# monitor-one-io-card-v0_0_4.net
KiCad netlist of a schematic drawn in EAGLE
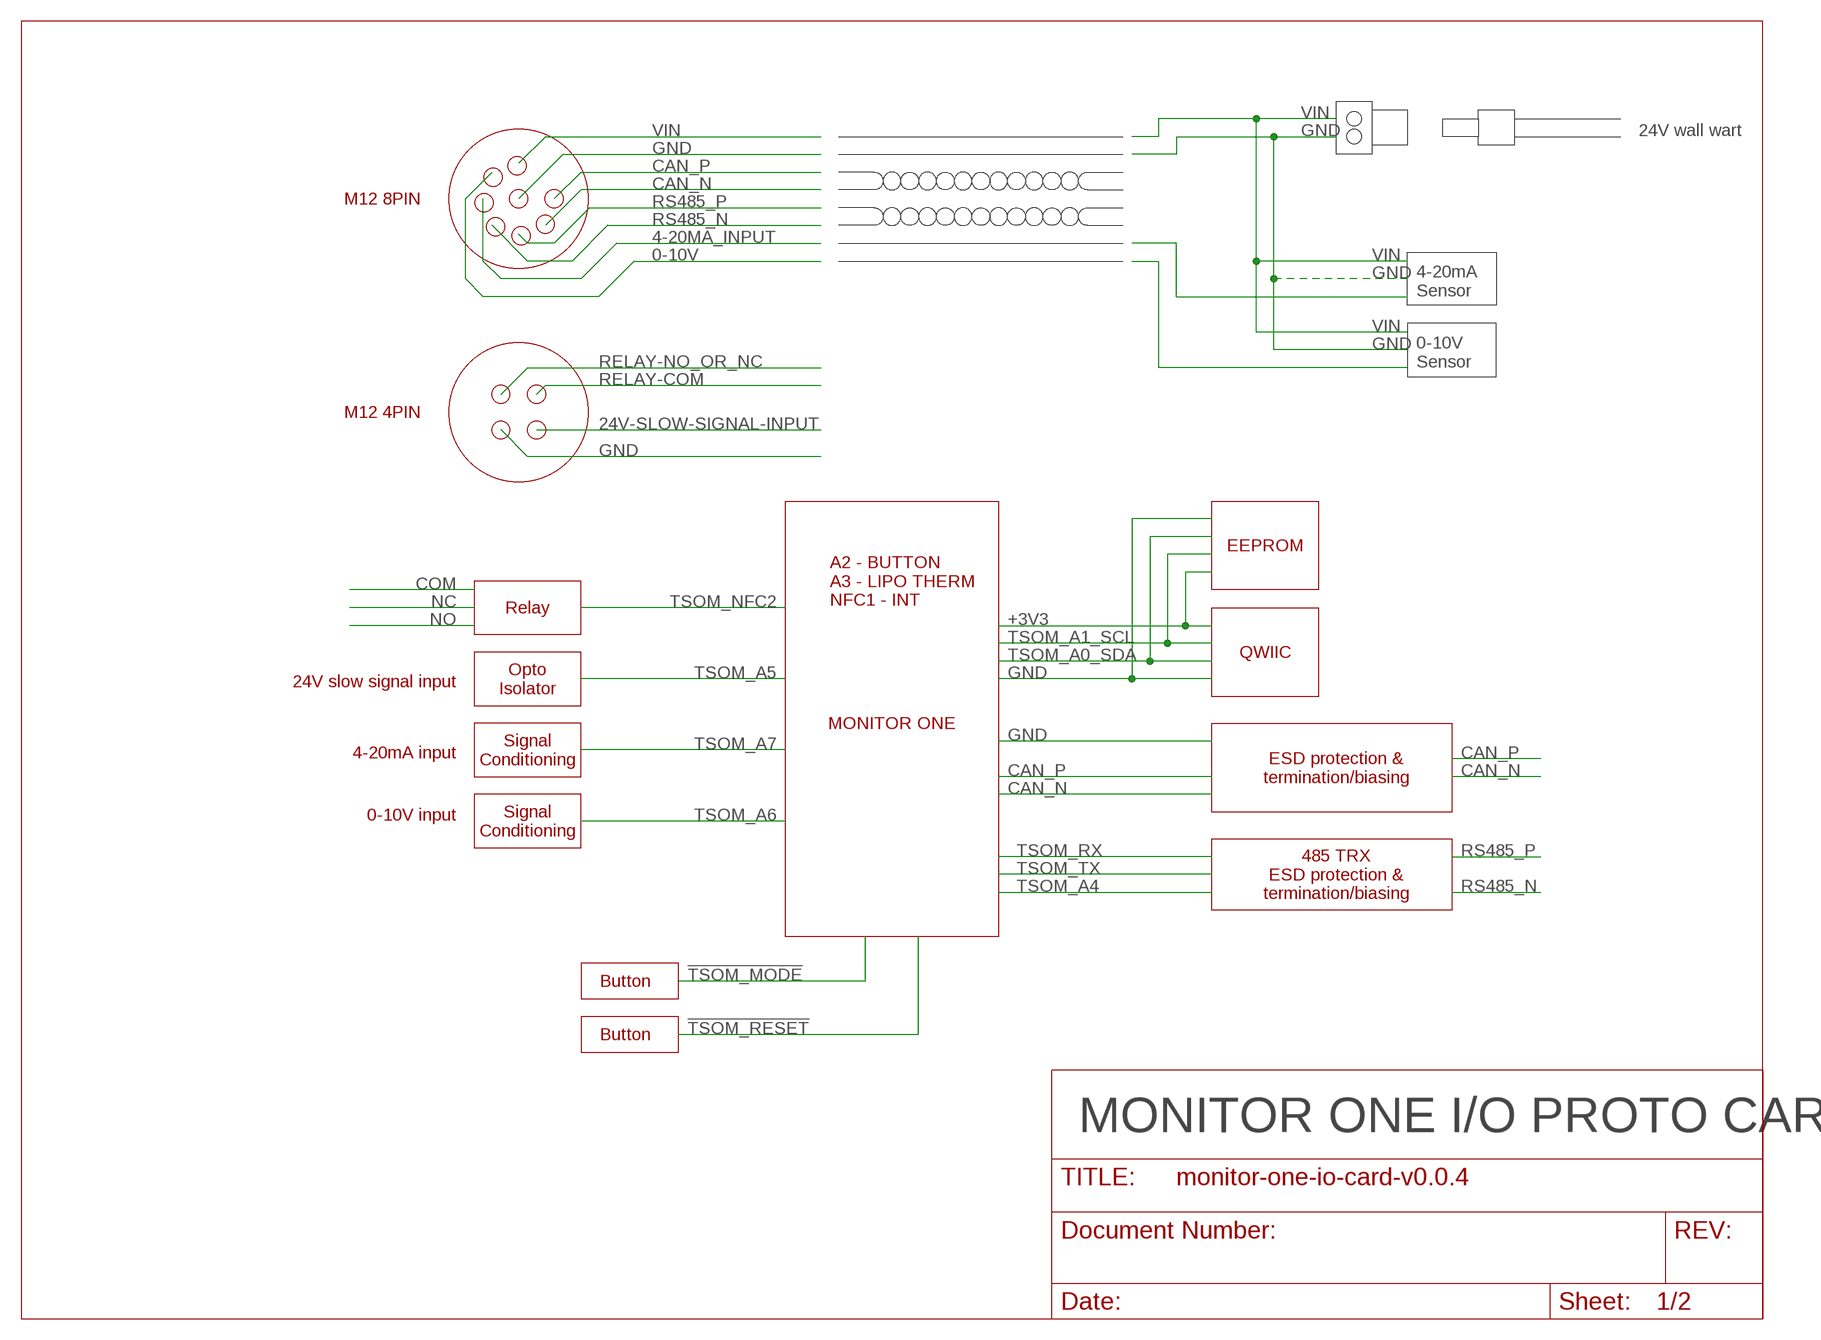
[diagram p0: schematic, sheet 1]
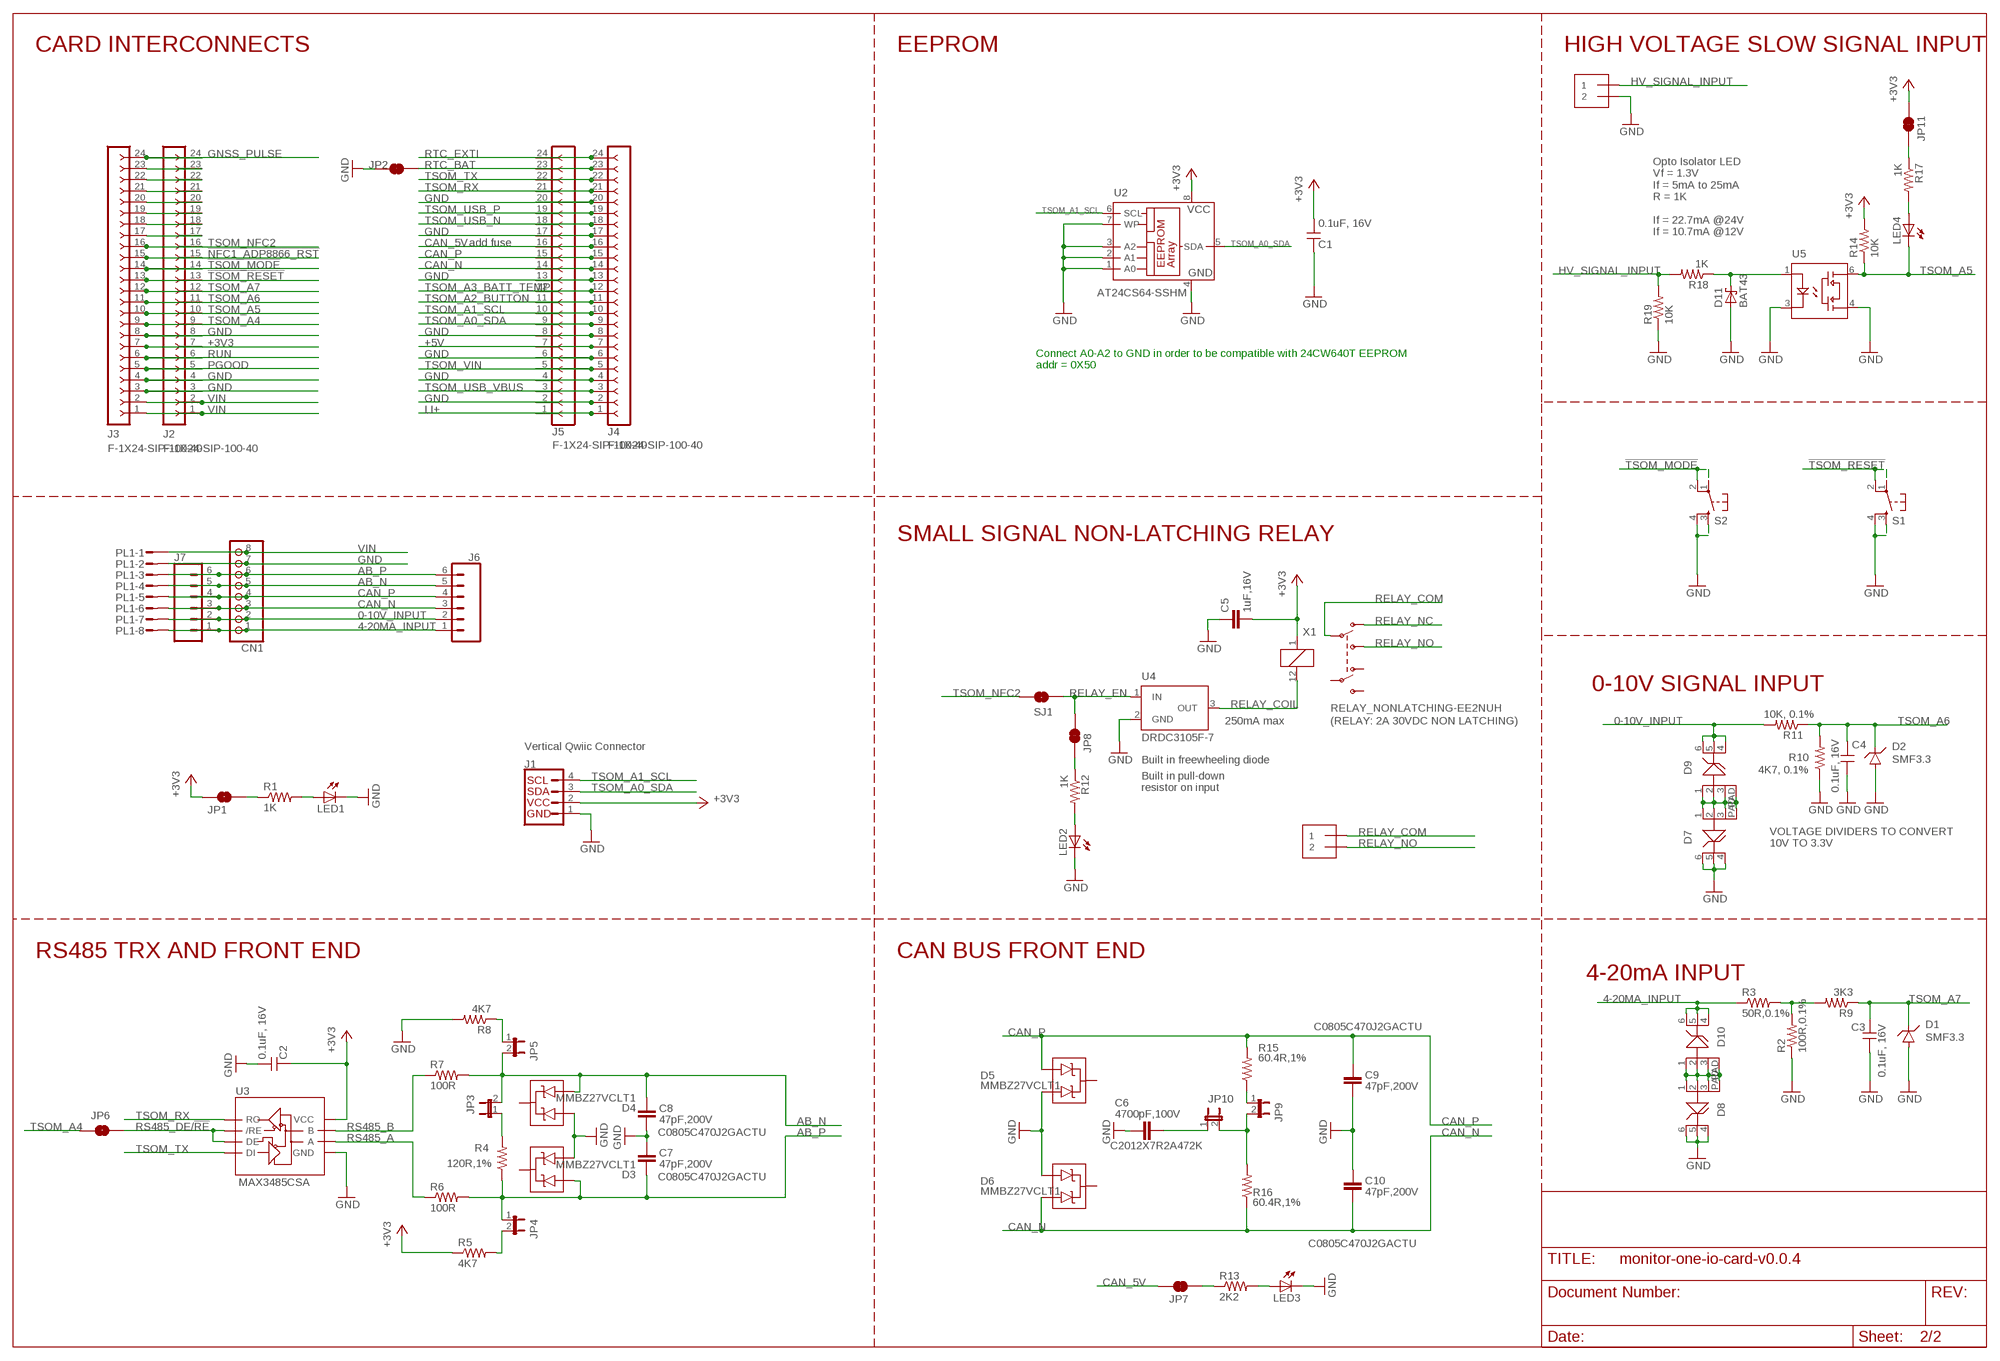
[diagram p1: schematic, sheet 2]

(export (version "E")
  (design (tool "Eeschema 10.0.6"))
  (components
    (comp (ref "C1")
      (value "0.1uF, 16V")
      (footprint "eagle-import:C0603_P")
      (fields (field (name "MFG") "FENGHUA") (field (name "MPN") "0603B104K160NT"))
      (libsource (lib "eagle-import") (part "CAP_06030.1UF_16V_"))
    )
    (comp (ref "C2")
      (value "0.1uF, 16V")
      (footprint "eagle-import:C0603_P")
      (fields (field (name "MFG") "FENGHUA") (field (name "MPN") "0603B104K160NT"))
      (libsource (lib "eagle-import") (part "CAP_06030.1UF_16V_"))
    )
    (comp (ref "C3")
      (value "0.1uF, 16V")
      (footprint "eagle-import:C0603_P")
      (fields (field (name "MFG") "FENGHUA") (field (name "MPN") "0603B104K160NT"))
      (libsource (lib "eagle-import") (part "CAP_06030.1UF_16V_"))
    )
    (comp (ref "C4")
      (value "0.1uF, 16V")
      (footprint "eagle-import:C0603_P")
      (fields (field (name "MFG") "FENGHUA") (field (name "MPN") "0603B104K160NT"))
      (libsource (lib "eagle-import") (part "CAP_06030.1UF_16V_"))
    )
    (comp (ref "C5")
      (value "1uF,16V")
      (footprint "eagle-import:C0805")
      (libsource (lib "eagle-import") (part "C-EUC0805"))
    )
    (comp (ref "C6")
      (value "4700pF,100V")
      (footprint "eagle-import:C0805")
      (fields (field (name "PART_NUMBER") "C2012X7R2A472K"))
      (libsource (lib "eagle-import") (part "C-EUC0805"))
    )
    (comp (ref "C7")
      (value "47pF,200V")
      (footprint "eagle-import:C0805")
      (fields (field (name "PART_NUMBER") "C0805C470J2GACTU"))
      (libsource (lib "eagle-import") (part "C-EUC0805"))
    )
    (comp (ref "C8")
      (value "47pF,200V")
      (footprint "eagle-import:C0805")
      (fields (field (name "PART_NUMBER") "C0805C470J2GACTU"))
      (libsource (lib "eagle-import") (part "C-EUC0805"))
    )
    (comp (ref "C9")
      (value "47pF,200V")
      (footprint "eagle-import:C0805")
      (fields
        (field (name "MFG") "KEMET")
        (field (name "MPN") "C0805C470J2GACTU")
        (field (name "PART_NUMBER") "C0805C470J2GACTU")
      )
      (libsource (lib "eagle-import") (part "C-EUC0805"))
    )
    (comp (ref "C10")
      (value "47pF,200V")
      (footprint "eagle-import:C0805")
      (fields
        (field (name "MFG") "KEMET")
        (field (name "MPN") "C0805C470J2GACTU")
        (field (name "PART_NUMBER") "C0805C470J2GACTU")
      )
      (libsource (lib "eagle-import") (part "C-EUC0805"))
    )
    (comp (ref "CN1")
      (value "JST_8PIN")
      (footprint "eagle-import:JSTPH8")
      (libsource (lib "eagle-import") (part "JST_8PIN"))
    )
    (comp (ref "D1")
      (value "SMF3.3")
      (footprint "eagle-import:SOD-123FL")
      (libsource (lib "eagle-import") (part "TVS-DIODE-SOD123FL"))
    )
    (comp (ref "D2")
      (value "SMF3.3")
      (footprint "eagle-import:SOD-123FL")
      (libsource (lib "eagle-import") (part "TVS-DIODE-SOD123FL"))
    )
    (comp (ref "D3")
      (value "MMBZ27VCLT1")
      (footprint "eagle-import:SOT23-3")
      (libsource (lib "eagle-import") (part "MMBZ27VCLT1"))
    )
    (comp (ref "D4")
      (value "MMBZ27VCLT1")
      (footprint "eagle-import:SOT23-3")
      (libsource (lib "eagle-import") (part "MMBZ27VCLT1"))
    )
    (comp (ref "D5")
      (value "MMBZ27VCLT1")
      (footprint "eagle-import:SOT23-3")
      (fields (field (name "MFG") "ON SEMI"))
      (libsource (lib "eagle-import") (part "MMBZ27VCLT1"))
    )
    (comp (ref "D6")
      (value "MMBZ27VCLT1")
      (footprint "eagle-import:SOT23-3")
      (fields (field (name "MFG") "ON SEMI"))
      (libsource (lib "eagle-import") (part "MMBZ27VCLT1"))
    )
    (comp (ref "D7")
      (value "TVS3300DRVRNO-GND-VIAS")
      (footprint "eagle-import:WSON-6-NO-GND-VIAS")
      (libsource (lib "eagle-import") (part "TVS3300DRVRNO-GND-VIAS"))
    )
    (comp (ref "D8")
      (value "TVS3300DRVRNO-GND-VIAS")
      (footprint "eagle-import:WSON-6-NO-GND-VIAS")
      (libsource (lib "eagle-import") (part "TVS3300DRVRNO-GND-VIAS"))
    )
    (comp (ref "D9")
      (value "TVS3300DRVRNO-GND-VIAS")
      (footprint "eagle-import:WSON-6-NO-GND-VIAS")
      (libsource (lib "eagle-import") (part "TVS3300DRVRNO-GND-VIAS"))
    )
    (comp (ref "D10")
      (value "TVS3300DRVRNO-GND-VIAS")
      (footprint "eagle-import:WSON-6-NO-GND-VIAS")
      (libsource (lib "eagle-import") (part "TVS3300DRVRNO-GND-VIAS"))
    )
    (comp (ref "D11")
      (value "BAT43")
      (footprint "eagle-import:SOD3718X135N")
      (libsource (lib "eagle-import") (part "SCHOTTKY_SOD-123"))
    )
    (comp (ref "J1")
      (value "Vertical Qwiic Connector")
      (footprint "eagle-import:JST04_1MM_VERT")
      (libsource (lib "eagle-import") (part "QWIIC_CONNECTOR"))
    )
    (comp (ref "J2")
      (value "F-1X24-SIP-100-40")
      (footprint "eagle-import:SIP-100-24-40")
      (libsource (lib "eagle-import") (part "F-1X24-SIP-100-40"))
    )
    (comp (ref "J3")
      (value "F-1X24-SIP-100-40")
      (footprint "eagle-import:SIP-100-24-40")
      (libsource (lib "eagle-import") (part "F-1X24-SIP-100-40"))
    )
    (comp (ref "J4")
      (value "F-1X24-SIP-100-40")
      (footprint "eagle-import:SIP-100-24-40")
      (libsource (lib "eagle-import") (part "F-1X24-SIP-100-40"))
    )
    (comp (ref "J5")
      (value "F-1X24-SIP-100-40")
      (footprint "eagle-import:SIP-100-24-40")
      (libsource (lib "eagle-import") (part "F-1X24-SIP-100-40"))
    )
    (comp (ref "J6")
      (value "CONN_06NO_SILK_NO_POP")
      (footprint "eagle-import:1X06_NO_SILK")
      (libsource (lib "eagle-import") (part "CONN_06NO_SILK_NO_POP"))
    )
    (comp (ref "J7")
      (value "CONN_06NO_SILK_NO_POP")
      (footprint "eagle-import:1X06_NO_SILK")
      (libsource (lib "eagle-import") (part "CONN_06NO_SILK_NO_POP"))
    )
    (comp (ref "J8")
      (value "1X2-3.5MM")
      (footprint "eagle-import:1X2-3.5MM")
      (libsource (lib "eagle-import") (part "1X2-3.5MM"))
    )
    (comp (ref "J9")
      (value "1X2-3.5MM")
      (footprint "eagle-import:1X2-3.5MM")
      (libsource (lib "eagle-import") (part "1X2-3.5MM"))
    )
    (comp (ref "JP1")
      (value "JUMPER-SMT_2_NC_TRACE_NO-SILK")
      (footprint "eagle-import:SMT-JUMPER_2_NC_TRACE_NO-SILK")
      (libsource (lib "eagle-import") (part "JUMPER-SMT_2_NC_TRACE_NO-SILK"))
    )
    (comp (ref "JP2")
      (value "JUMPER-SMT_2_NC_TRACE_NO-SILK")
      (footprint "eagle-import:SMT-JUMPER_2_NC_TRACE_NO-SILK")
      (libsource (lib "eagle-import") (part "JUMPER-SMT_2_NC_TRACE_NO-SILK"))
    )
    (comp (ref "JP3")
      (value "JUMPER2")
      (footprint "eagle-import:JUMPER2")
      (libsource (lib "eagle-import") (part "JUMPER2"))
    )
    (comp (ref "JP4")
      (value "JUMPER2")
      (footprint "eagle-import:JUMPER2")
      (libsource (lib "eagle-import") (part "JUMPER2"))
    )
    (comp (ref "JP5")
      (value "JUMPER2")
      (footprint "eagle-import:JUMPER2")
      (libsource (lib "eagle-import") (part "JUMPER2"))
    )
    (comp (ref "JP6")
      (value "JUMPER-SMT_2_NC_TRACE_NO-SILK")
      (footprint "eagle-import:SMT-JUMPER_2_NC_TRACE_NO-SILK")
      (libsource (lib "eagle-import") (part "JUMPER-SMT_2_NC_TRACE_NO-SILK"))
    )
    (comp (ref "JP7")
      (value "JUMPER-SMT_2_NC_TRACE_NO-SILK")
      (footprint "eagle-import:SMT-JUMPER_2_NC_TRACE_NO-SILK")
      (libsource (lib "eagle-import") (part "JUMPER-SMT_2_NC_TRACE_NO-SILK"))
    )
    (comp (ref "JP8")
      (value "JUMPER-SMT_2_NC_TRACE_NO-SILK")
      (footprint "eagle-import:SMT-JUMPER_2_NC_TRACE_NO-SILK")
      (libsource (lib "eagle-import") (part "JUMPER-SMT_2_NC_TRACE_NO-SILK"))
    )
    (comp (ref "JP9")
      (value "JUMPER2")
      (footprint "eagle-import:JUMPER2")
      (libsource (lib "eagle-import") (part "JUMPER2"))
    )
    (comp (ref "JP10")
      (value "JUMPER2")
      (footprint "eagle-import:JUMPER2")
      (libsource (lib "eagle-import") (part "JUMPER2"))
    )
    (comp (ref "JP11")
      (value "JUMPER-SMT_2_NC_TRACE_NO-SILK")
      (footprint "eagle-import:SMT-JUMPER_2_NC_TRACE_NO-SILK")
      (libsource (lib "eagle-import") (part "JUMPER-SMT_2_NC_TRACE_NO-SILK"))
    )
    (comp (ref "LED1")
      (value "LEDCHIP-LED0603")
      (footprint "eagle-import:CHIP-LED0603")
      (libsource (lib "eagle-import") (part "LEDCHIP-LED0603"))
    )
    (comp (ref "LED2")
      (value "LEDCHIP-LED0603")
      (footprint "eagle-import:CHIP-LED0603")
      (libsource (lib "eagle-import") (part "LEDCHIP-LED0603"))
    )
    (comp (ref "LED3")
      (value "LEDCHIP-LED0603")
      (footprint "eagle-import:CHIP-LED0603")
      (libsource (lib "eagle-import") (part "LEDCHIP-LED0603"))
    )
    (comp (ref "LED4")
      (value "LEDCHIP-LED0603")
      (footprint "eagle-import:CHIP-LED0603")
      (libsource (lib "eagle-import") (part "LEDCHIP-LED0603"))
    )
    (comp (ref "PL1")
      (value "DF3-08R")
      (footprint "eagle-import:DF3R-08")
      (libsource (lib "eagle-import") (part "DF3-08R"))
    )
    (comp (ref "R1")
      (value "1K")
      (footprint "eagle-import:R0603_P")
      (fields (field (name "MFG") "FENGHUA") (field (name "MPN") "RC-03K102FT"))
      (libsource (lib "eagle-import") (part "RES_06031K_"))
    )
    (comp (ref "R2")
      (value "100R,0.1%")
      (footprint "eagle-import:R0805")
      (libsource (lib "eagle-import") (part "R-US_R0805"))
    )
    (comp (ref "R3")
      (value "50R,0.1%")
      (footprint "eagle-import:R0805")
      (libsource (lib "eagle-import") (part "R-US_R0805"))
    )
    (comp (ref "R4")
      (value "120R,1%")
      (footprint "eagle-import:R1206")
      (libsource (lib "eagle-import") (part "R-US_R1206"))
    )
    (comp (ref "R5")
      (value "4K7")
      (footprint "eagle-import:R0603_P")
      (fields (field (name "MFG") "YAGEO") (field (name "MPN") "RC0603FR-074K7L"))
      (libsource (lib "eagle-import") (part "RES_06034K7_"))
    )
    (comp (ref "R6")
      (value "100R")
      (footprint "eagle-import:R0603_P")
      (libsource (lib "eagle-import") (part "RES_0603"))
    )
    (comp (ref "R7")
      (value "100R")
      (footprint "eagle-import:R0603_P")
      (libsource (lib "eagle-import") (part "RES_0603"))
    )
    (comp (ref "R8")
      (value "4K7")
      (footprint "eagle-import:R0603_P")
      (fields (field (name "MFG") "YAGEO") (field (name "MPN") "RC0603FR-074K7L"))
      (libsource (lib "eagle-import") (part "RES_06034K7_"))
    )
    (comp (ref "R9")
      (value "3K3")
      (footprint "eagle-import:R0603_P")
      (libsource (lib "eagle-import") (part "RES_0603"))
    )
    (comp (ref "R10")
      (value "4K7, 0.1%")
      (footprint "eagle-import:R0603_P")
      (libsource (lib "eagle-import") (part "RES_0603"))
    )
    (comp (ref "R11")
      (value "10K, 0.1%")
      (footprint "eagle-import:R0603_P")
      (fields (field (name "MFG") "YAGEO") (field (name "MPN") "RC0603FR-0710KL"))
      (libsource (lib "eagle-import") (part "RES_060310K_"))
    )
    (comp (ref "R12")
      (value "1K")
      (footprint "eagle-import:R0603_P")
      (fields (field (name "MFG") "FENGHUA") (field (name "MPN") "RC-03K102FT"))
      (libsource (lib "eagle-import") (part "RES_06031K_"))
    )
    (comp (ref "R13")
      (value "2K2")
      (footprint "eagle-import:R0603_P")
      (libsource (lib "eagle-import") (part "RES_06032K2_"))
    )
    (comp (ref "R14")
      (value "10K")
      (footprint "eagle-import:R0603_P")
      (fields (field (name "MFG") "YAGEO") (field (name "MPN") "RC0603FR-0710KL"))
      (libsource (lib "eagle-import") (part "RES_060310K_"))
    )
    (comp (ref "R15")
      (value "60.4R,1%")
      (footprint "eagle-import:R1206")
      (libsource (lib "eagle-import") (part "R-US_R1206"))
    )
    (comp (ref "R16")
      (value "60.4R,1%")
      (footprint "eagle-import:R1206")
      (libsource (lib "eagle-import") (part "R-US_R1206"))
    )
    (comp (ref "R17")
      (value "1K")
      (footprint "eagle-import:R0603_P")
      (fields (field (name "MFG") "FENGHUA") (field (name "MPN") "RC-03K102FT"))
      (libsource (lib "eagle-import") (part "RES_06031K_"))
    )
    (comp (ref "R18")
      (value "1K")
      (footprint "eagle-import:R0603_P")
      (fields (field (name "MFG") "FENGHUA") (field (name "MPN") "RC-03K102FT"))
      (libsource (lib "eagle-import") (part "RES_06031K_"))
    )
    (comp (ref "R19")
      (value "10K")
      (footprint "eagle-import:R0603_P")
      (fields (field (name "MFG") "YAGEO") (field (name "MPN") "RC0603FR-0710KL"))
      (libsource (lib "eagle-import") (part "RES_060310K_"))
    )
    (comp (ref "S1")
      (value "TAC_SWITCHSMD")
      (footprint "eagle-import:TACTILE_SWITCH_SMD")
      (libsource (lib "eagle-import") (part "TAC_SWITCHSMD"))
    )
    (comp (ref "S2")
      (value "TAC_SWITCHSMD")
      (footprint "eagle-import:TACTILE_SWITCH_SMD")
      (libsource (lib "eagle-import") (part "TAC_SWITCHSMD"))
    )
    (comp (ref "SJ1")
      (value "JUMPER-SMT_2_NC_TRACE_NO-SILK")
      (footprint "eagle-import:SMT-JUMPER_2_NC_TRACE_NO-SILK")
      (libsource (lib "eagle-import") (part "JUMPER-SMT_2_NC_TRACE_NO-SILK"))
    )
    (comp (ref "U2")
      (value "AT24CS64-SSHM")
      (footprint "eagle-import:SO-08")
      (fields (field (name "MF") "MICROCHIP") (field (name "MPN") "24AA01/SN"))
      (libsource (lib "eagle-import") (part "24SNAA01"))
    )
    (comp (ref "U3")
      (value "MAX3485CSA")
      (footprint "eagle-import:SO08")
      (libsource (lib "eagle-import") (part "RS485SOIC"))
    )
    (comp (ref "U4")
      (value "DRDC3105F-7")
      (footprint "eagle-import:SOT23")
      (libsource (lib "eagle-import") (part "DRDC3105F-7"))
    )
    (comp (ref "U5")
      (value "U5")
      (footprint "eagle-import:TLP172A")
      (libsource (lib "eagle-import") (part "TLP172AM"))
    )
    (comp (ref "X1")
      (value "RELAY_NONLATCHING-EE2NUH")
      (footprint "eagle-import:RELAY_EE2_NOLATCH")
      (libsource (lib "eagle-import") (part "RELAY_NONLATCHING-EE2NUH"))
    )
  )
  (nets
    (net (code "1") (name "+3V3") (class "Default")
      (node (ref "C1") (pin "1") (pinfunction "1_1") (pintype "bidirectional"))
      (node (ref "C2") (pin "2") (pinfunction "2_2") (pintype "bidirectional"))
      (node (ref "C5") (pin "2") (pinfunction "2_2") (pintype "passive"))
      (node (ref "J1") (pin "2") (pinfunction "2_2") (pintype "power_in"))
      (node (ref "J2") (pin "7") (pinfunction "7_7") (pintype "passive"))
      (node (ref "J3") (pin "7") (pinfunction "7_7") (pintype "passive"))
      (node (ref "JP1") (pin "1") (pinfunction "1_1") (pintype "passive"))
      (node (ref "JP11") (pin "2") (pinfunction "2_2") (pintype "passive"))
      (node (ref "R14") (pin "2") (pinfunction "2_2") (pintype "passive"))
      (node (ref "R5") (pin "1") (pinfunction "1_1") (pintype "passive"))
      (node (ref "U2") (pin "8") (pinfunction "VCC_8") (pintype "power_in"))
      (node (ref "U3") (pin "8") (pinfunction "VCC_8") (pintype "bidirectional"))
      (node (ref "X1") (pin "1") (pinfunction "1_1") (pintype "passive"))
    )
    (net (code "2") (name "+5V") (class "Default")
      (node (ref "J4") (pin "7") (pinfunction "7_7") (pintype "passive"))
      (node (ref "J5") (pin "7") (pinfunction "7_7") (pintype "passive"))
    )
    (net (code "4") (name "0-10V_INPUT") (class "Default")
      (node (ref "CN1") (pin "2") (pinfunction "2_2") (pintype "passive"))
      (node (ref "D9") (pin "4") (pinfunction "IN_4") (pintype "bidirectional"))
      (node (ref "D9") (pin "5") (pinfunction "IN_5") (pintype "bidirectional"))
      (node (ref "D9") (pin "6") (pinfunction "IN_6") (pintype "bidirectional"))
      (node (ref "J6") (pin "2") (pinfunction "2_2") (pintype "passive"))
      (node (ref "J7") (pin "2") (pinfunction "2_2") (pintype "passive"))
      (node (ref "PL1") (pin "7") (pinfunction "S_7") (pintype "passive"))
      (node (ref "R11") (pin "2") (pinfunction "2_2") (pintype "passive"))
    )
    (net (code "5") (name "4-20MA_INPUT") (class "Default")
      (node (ref "CN1") (pin "1") (pinfunction "1_1") (pintype "passive"))
      (node (ref "D10") (pin "4") (pinfunction "IN_4") (pintype "bidirectional"))
      (node (ref "D10") (pin "5") (pinfunction "IN_5") (pintype "bidirectional"))
      (node (ref "D10") (pin "6") (pinfunction "IN_6") (pintype "bidirectional"))
      (node (ref "J6") (pin "1") (pinfunction "1_1") (pintype "passive"))
      (node (ref "J7") (pin "1") (pinfunction "1_1") (pintype "passive"))
      (node (ref "PL1") (pin "8") (pinfunction "S_8") (pintype "passive"))
      (node (ref "R3") (pin "1") (pinfunction "1_1") (pintype "passive"))
    )
    (net (code "7") (name "AB_N") (class "Default")
      (node (ref "C8") (pin "1") (pinfunction "1_1") (pintype "passive"))
      (node (ref "CN1") (pin "5") (pinfunction "5_5") (pintype "passive"))
      (node (ref "D4") (pin "1") (pinfunction "A1_1") (pintype "passive"))
      (node (ref "J6") (pin "5") (pinfunction "5_5") (pintype "passive"))
      (node (ref "J7") (pin "5") (pinfunction "5_5") (pintype "passive"))
      (node (ref "JP3") (pin "2") (pinfunction "2_2") (pintype "passive"))
      (node (ref "JP5") (pin "2") (pinfunction "2_2") (pintype "passive"))
      (node (ref "PL1") (pin "4") (pinfunction "S_4") (pintype "passive"))
      (node (ref "R7") (pin "2") (pinfunction "2_2") (pintype "passive"))
    )
    (net (code "8") (name "AB_P") (class "Default")
      (node (ref "C7") (pin "2") (pinfunction "2_2") (pintype "passive"))
      (node (ref "CN1") (pin "6") (pinfunction "6_6") (pintype "passive"))
      (node (ref "D3") (pin "2") (pinfunction "A2_2") (pintype "passive"))
      (node (ref "J6") (pin "6") (pinfunction "6_6") (pintype "passive"))
      (node (ref "J7") (pin "6") (pinfunction "6_6") (pintype "passive"))
      (node (ref "JP4") (pin "1") (pinfunction "1_1") (pintype "passive"))
      (node (ref "PL1") (pin "3") (pinfunction "S_3") (pintype "passive"))
      (node (ref "R4") (pin "1") (pinfunction "1_1") (pintype "passive"))
      (node (ref "R6") (pin "2") (pinfunction "2_2") (pintype "passive"))
    )
    (net (code "9") (name "CAN_5V") (class "Default")
      (node (ref "J4") (pin "16") (pinfunction "16_16") (pintype "passive"))
      (node (ref "J5") (pin "16") (pinfunction "16_16") (pintype "passive"))
      (node (ref "JP7") (pin "1") (pinfunction "1_1") (pintype "passive"))
    )
    (net (code "10") (name "CAN_N") (class "Default")
      (node (ref "C10") (pin "2") (pinfunction "2_2") (pintype "passive"))
      (node (ref "CN1") (pin "3") (pinfunction "3_3") (pintype "passive"))
      (node (ref "D6") (pin "1") (pinfunction "A1_1") (pintype "passive"))
      (node (ref "J4") (pin "14") (pinfunction "14_14") (pintype "passive"))
      (node (ref "J5") (pin "14") (pinfunction "14_14") (pintype "passive"))
      (node (ref "J6") (pin "3") (pinfunction "3_3") (pintype "passive"))
      (node (ref "J7") (pin "3") (pinfunction "3_3") (pintype "passive"))
      (node (ref "PL1") (pin "6") (pinfunction "S_6") (pintype "passive"))
      (node (ref "R16") (pin "1") (pinfunction "1_1") (pintype "passive"))
    )
    (net (code "11") (name "CAN_P") (class "Default")
      (node (ref "C9") (pin "1") (pinfunction "1_1") (pintype "passive"))
      (node (ref "CN1") (pin "4") (pinfunction "4_4") (pintype "passive"))
      (node (ref "D5") (pin "2") (pinfunction "A2_2") (pintype "passive"))
      (node (ref "J4") (pin "15") (pinfunction "15_15") (pintype "passive"))
      (node (ref "J5") (pin "15") (pinfunction "15_15") (pintype "passive"))
      (node (ref "J6") (pin "4") (pinfunction "4_4") (pintype "passive"))
      (node (ref "J7") (pin "4") (pinfunction "4_4") (pintype "passive"))
      (node (ref "PL1") (pin "5") (pinfunction "S_5") (pintype "passive"))
      (node (ref "R15") (pin "2") (pinfunction "2_2") (pintype "passive"))
    )
    (net (code "13") (name "GND") (class "Default")
      (node (ref "C1") (pin "2") (pinfunction "2_2") (pintype "bidirectional"))
      (node (ref "C10") (pin "1") (pinfunction "1_1") (pintype "passive"))
      (node (ref "C2") (pin "1") (pinfunction "1_1") (pintype "bidirectional"))
      (node (ref "C3") (pin "1") (pinfunction "1_1") (pintype "bidirectional"))
      (node (ref "C4") (pin "2") (pinfunction "2_2") (pintype "bidirectional"))
      (node (ref "C5") (pin "1") (pinfunction "1_1") (pintype "passive"))
      (node (ref "C6") (pin "1") (pinfunction "1_1") (pintype "passive"))
      (node (ref "C7") (pin "1") (pinfunction "1_1") (pintype "passive"))
      (node (ref "C8") (pin "2") (pinfunction "2_2") (pintype "passive"))
      (node (ref "C9") (pin "2") (pinfunction "2_2") (pintype "passive"))
      (node (ref "CN1") (pin "7") (pinfunction "7_7") (pintype "passive"))
      (node (ref "D1") (pin "A") (pinfunction "A_A") (pintype "passive"))
      (node (ref "D11") (pin "A") (pinfunction "A_A") (pintype "passive"))
      (node (ref "D2") (pin "A") (pinfunction "A_A") (pintype "passive"))
      (node (ref "D3") (pin "1") (pinfunction "A1_1") (pintype "passive"))
      (node (ref "D4") (pin "2") (pinfunction "A2_2") (pintype "passive"))
      (node (ref "D5") (pin "1") (pinfunction "A1_1") (pintype "passive"))
      (node (ref "D6") (pin "2") (pinfunction "A2_2") (pintype "passive"))
      (node (ref "D7") (pin "4") (pinfunction "IN_4") (pintype "bidirectional"))
      (node (ref "D7") (pin "5") (pinfunction "IN_5") (pintype "bidirectional"))
      (node (ref "D7") (pin "6") (pinfunction "IN_6") (pintype "bidirectional"))
      (node (ref "D8") (pin "4") (pinfunction "IN_4") (pintype "bidirectional"))
      (node (ref "D8") (pin "5") (pinfunction "IN_5") (pintype "bidirectional"))
      (node (ref "D8") (pin "6") (pinfunction "IN_6") (pintype "bidirectional"))
      (node (ref "J1") (pin "1") (pinfunction "1_1") (pintype "power_in"))
      (node (ref "J2") (pin "3") (pinfunction "3_3") (pintype "passive"))
      (node (ref "J2") (pin "4") (pinfunction "4_4") (pintype "passive"))
      (node (ref "J2") (pin "8") (pinfunction "8_8") (pintype "passive"))
      (node (ref "J3") (pin "3") (pinfunction "3_3") (pintype "passive"))
      (node (ref "J3") (pin "4") (pinfunction "4_4") (pintype "passive"))
      (node (ref "J3") (pin "8") (pinfunction "8_8") (pintype "passive"))
      (node (ref "J4") (pin "13") (pinfunction "13_13") (pintype "passive"))
      (node (ref "J4") (pin "17") (pinfunction "17_17") (pintype "passive"))
      (node (ref "J4") (pin "2") (pinfunction "2_2") (pintype "passive"))
      (node (ref "J4") (pin "20") (pinfunction "20_20") (pintype "passive"))
      (node (ref "J4") (pin "4") (pinfunction "4_4") (pintype "passive"))
      (node (ref "J4") (pin "6") (pinfunction "6_6") (pintype "passive"))
      (node (ref "J4") (pin "8") (pinfunction "8_8") (pintype "passive"))
      (node (ref "J5") (pin "13") (pinfunction "13_13") (pintype "passive"))
      (node (ref "J5") (pin "17") (pinfunction "17_17") (pintype "passive"))
      (node (ref "J5") (pin "2") (pinfunction "2_2") (pintype "passive"))
      (node (ref "J5") (pin "20") (pinfunction "20_20") (pintype "passive"))
      (node (ref "J5") (pin "4") (pinfunction "4_4") (pintype "passive"))
      (node (ref "J5") (pin "6") (pinfunction "6_6") (pintype "passive"))
      (node (ref "J5") (pin "8") (pinfunction "8_8") (pintype "passive"))
      (node (ref "J8") (pin "2") (pinfunction "2_2") (pintype "passive"))
      (node (ref "JP2") (pin "1") (pinfunction "1_1") (pintype "passive"))
      (node (ref "LED1") (pin "C") (pinfunction "C_C") (pintype "passive"))
      (node (ref "LED2") (pin "C") (pinfunction "C_C") (pintype "passive"))
      (node (ref "LED3") (pin "C") (pinfunction "C_C") (pintype "passive"))
      (node (ref "PL1") (pin "2") (pinfunction "S_2") (pintype "passive"))
      (node (ref "R10") (pin "1") (pinfunction "1_1") (pintype "passive"))
      (node (ref "R19") (pin "1") (pinfunction "1_1") (pintype "passive"))
      (node (ref "R2") (pin "1") (pinfunction "1_1") (pintype "passive"))
      (node (ref "R8") (pin "2") (pinfunction "2_2") (pintype "passive"))
      (node (ref "S1") (pin "3") (pinfunction "3_3") (pintype "passive"))
      (node (ref "S1") (pin "4") (pinfunction "4_4") (pintype "passive"))
      (node (ref "S2") (pin "3") (pinfunction "3_3") (pintype "passive"))
      (node (ref "S2") (pin "4") (pinfunction "4_4") (pintype "passive"))
      (node (ref "U2") (pin "1") (pinfunction "A0_1") (pintype "input"))
      (node (ref "U2") (pin "2") (pinfunction "A1_2") (pintype "input"))
      (node (ref "U2") (pin "3") (pinfunction "A2_3") (pintype "input"))
      (node (ref "U2") (pin "4") (pinfunction "GND_4") (pintype "power_in"))
      (node (ref "U2") (pin "7") (pinfunction "WP_7") (pintype "input"))
      (node (ref "U3") (pin "5") (pinfunction "GND_5") (pintype "bidirectional"))
      (node (ref "U4") (pin "2") (pinfunction "GND_2") (pintype "bidirectional"))
      (node (ref "U5") (pin "3") (pinfunction "3_3") (pintype "bidirectional"))
      (node (ref "U5") (pin "4") (pinfunction "4_4") (pintype "bidirectional"))
    )
    (net (code "14") (name "GNSS_PULSE") (class "Default")
      (node (ref "J2") (pin "24") (pinfunction "24_24") (pintype "passive"))
      (node (ref "J3") (pin "24") (pinfunction "24_24") (pintype "passive"))
    )
    (net (code "15") (name "HV_SIGNAL_INPUT") (class "Default")
      (node (ref "J8") (pin "1") (pinfunction "1_1") (pintype "passive"))
      (node (ref "R18") (pin "2") (pinfunction "2_2") (pintype "passive"))
      (node (ref "R19") (pin "2") (pinfunction "2_2") (pintype "passive"))
    )
    (net (code "16") (name "LI+") (class "Default")
      (node (ref "J4") (pin "1") (pinfunction "1_1") (pintype "passive"))
      (node (ref "J5") (pin "1") (pinfunction "1_1") (pintype "passive"))
    )
    (net (code "19") (name "Net-(C6-Pad2)") (class "Default")
      (node (ref "C6") (pin "2") (pinfunction "2_2") (pintype "passive"))
      (node (ref "JP10") (pin "1") (pinfunction "1_1") (pintype "passive"))
    )
    (net (code "20") (name "Net-(D7-GND-Pad1)") (class "Default")
      (node (ref "D7") (pin "1") (pinfunction "GND_1") (pintype "bidirectional"))
      (node (ref "D7") (pin "2") (pinfunction "GND_2") (pintype "bidirectional"))
      (node (ref "D7") (pin "3") (pinfunction "GND_3") (pintype "bidirectional"))
      (node (ref "D7") (pin "PAD") (pinfunction "PAD_PAD") (pintype "bidirectional"))
      (node (ref "D9") (pin "1") (pinfunction "GND_1") (pintype "bidirectional"))
      (node (ref "D9") (pin "2") (pinfunction "GND_2") (pintype "bidirectional"))
      (node (ref "D9") (pin "3") (pinfunction "GND_3") (pintype "bidirectional"))
      (node (ref "D9") (pin "PAD") (pinfunction "PAD_PAD") (pintype "bidirectional"))
    )
    (net (code "21") (name "Net-(D10-GND-Pad1)") (class "Default")
      (node (ref "D10") (pin "1") (pinfunction "GND_1") (pintype "bidirectional"))
      (node (ref "D10") (pin "2") (pinfunction "GND_2") (pintype "bidirectional"))
      (node (ref "D10") (pin "3") (pinfunction "GND_3") (pintype "bidirectional"))
      (node (ref "D10") (pin "PAD") (pinfunction "PAD_PAD") (pintype "bidirectional"))
      (node (ref "D8") (pin "1") (pinfunction "GND_1") (pintype "bidirectional"))
      (node (ref "D8") (pin "2") (pinfunction "GND_2") (pintype "bidirectional"))
      (node (ref "D8") (pin "3") (pinfunction "GND_3") (pintype "bidirectional"))
      (node (ref "D8") (pin "PAD") (pinfunction "PAD_PAD") (pintype "bidirectional"))
    )
    (net (code "22") (name "Net-(D11-PadK)") (class "Default")
      (node (ref "D11") (pin "K") (pinfunction "K_K") (pintype "passive"))
      (node (ref "R18") (pin "1") (pinfunction "1_1") (pintype "passive"))
      (node (ref "U5") (pin "1") (pinfunction "1_1") (pintype "bidirectional"))
    )
    (net (code "23") (name "Net-(J2-Pad17)") (class "Default")
      (node (ref "J2") (pin "17") (pinfunction "17_17") (pintype "passive"))
      (node (ref "J3") (pin "17") (pinfunction "17_17") (pintype "passive"))
    )
    (net (code "24") (name "Net-(J2-Pad18)") (class "Default")
      (node (ref "J2") (pin "18") (pinfunction "18_18") (pintype "passive"))
      (node (ref "J3") (pin "18") (pinfunction "18_18") (pintype "passive"))
    )
    (net (code "25") (name "Net-(J2-Pad19)") (class "Default")
      (node (ref "J2") (pin "19") (pinfunction "19_19") (pintype "passive"))
      (node (ref "J3") (pin "19") (pinfunction "19_19") (pintype "passive"))
    )
    (net (code "26") (name "Net-(J2-Pad20)") (class "Default")
      (node (ref "J2") (pin "20") (pinfunction "20_20") (pintype "passive"))
      (node (ref "J3") (pin "20") (pinfunction "20_20") (pintype "passive"))
    )
    (net (code "27") (name "Net-(J2-Pad21)") (class "Default")
      (node (ref "J2") (pin "21") (pinfunction "21_21") (pintype "passive"))
      (node (ref "J3") (pin "21") (pinfunction "21_21") (pintype "passive"))
    )
    (net (code "28") (name "Net-(J2-Pad22)") (class "Default")
      (node (ref "J2") (pin "22") (pinfunction "22_22") (pintype "passive"))
      (node (ref "J3") (pin "22") (pinfunction "22_22") (pintype "passive"))
    )
    (net (code "29") (name "Net-(J2-Pad23)") (class "Default")
      (node (ref "J2") (pin "23") (pinfunction "23_23") (pintype "passive"))
      (node (ref "J3") (pin "23") (pinfunction "23_23") (pintype "passive"))
    )
    (net (code "30") (name "Net-(JP1-Pad2)") (class "Default")
      (node (ref "JP1") (pin "2") (pinfunction "2_2") (pintype "passive"))
      (node (ref "R1") (pin "1") (pinfunction "1_1") (pintype "passive"))
    )
    (net (code "31") (name "Net-(JP3-Pad1)") (class "Default")
      (node (ref "JP3") (pin "1") (pinfunction "1_1") (pintype "passive"))
      (node (ref "R4") (pin "2") (pinfunction "2_2") (pintype "passive"))
    )
    (net (code "32") (name "Net-(JP4-Pad2)") (class "Default")
      (node (ref "JP4") (pin "2") (pinfunction "2_2") (pintype "passive"))
      (node (ref "R5") (pin "2") (pinfunction "2_2") (pintype "passive"))
    )
    (net (code "33") (name "Net-(JP5-Pad1)") (class "Default")
      (node (ref "JP5") (pin "1") (pinfunction "1_1") (pintype "passive"))
      (node (ref "R8") (pin "1") (pinfunction "1_1") (pintype "passive"))
    )
    (net (code "34") (name "Net-(JP7-Pad2)") (class "Default")
      (node (ref "JP7") (pin "2") (pinfunction "2_2") (pintype "passive"))
      (node (ref "R13") (pin "1") (pinfunction "1_1") (pintype "passive"))
    )
    (net (code "35") (name "Net-(JP8-Pad1)") (class "Default")
      (node (ref "JP8") (pin "1") (pinfunction "1_1") (pintype "passive"))
      (node (ref "R12") (pin "1") (pinfunction "1_1") (pintype "passive"))
    )
    (net (code "36") (name "Net-(JP9-Pad1)") (class "Default")
      (node (ref "JP9") (pin "1") (pinfunction "1_1") (pintype "passive"))
      (node (ref "R15") (pin "1") (pinfunction "1_1") (pintype "passive"))
    )
    (net (code "37") (name "Net-(JP10-Pad2)") (class "Default")
      (node (ref "JP10") (pin "2") (pinfunction "2_2") (pintype "passive"))
      (node (ref "JP9") (pin "2") (pinfunction "2_2") (pintype "passive"))
      (node (ref "R16") (pin "2") (pinfunction "2_2") (pintype "passive"))
    )
    (net (code "38") (name "Net-(JP11-Pad1)") (class "Default")
      (node (ref "JP11") (pin "1") (pinfunction "1_1") (pintype "passive"))
      (node (ref "R17") (pin "1") (pinfunction "1_1") (pintype "passive"))
    )
    (net (code "39") (name "Net-(LED1-PadA)") (class "Default")
      (node (ref "LED1") (pin "A") (pinfunction "A_A") (pintype "passive"))
      (node (ref "R1") (pin "2") (pinfunction "2_2") (pintype "passive"))
    )
    (net (code "40") (name "Net-(LED2-PadA)") (class "Default")
      (node (ref "LED2") (pin "A") (pinfunction "A_A") (pintype "passive"))
      (node (ref "R12") (pin "2") (pinfunction "2_2") (pintype "passive"))
    )
    (net (code "41") (name "Net-(LED3-PadA)") (class "Default")
      (node (ref "LED3") (pin "A") (pinfunction "A_A") (pintype "passive"))
      (node (ref "R13") (pin "2") (pinfunction "2_2") (pintype "passive"))
    )
    (net (code "42") (name "Net-(LED4-PadA)") (class "Default")
      (node (ref "LED4") (pin "A") (pinfunction "A_A") (pintype "passive"))
      (node (ref "R17") (pin "2") (pinfunction "2_2") (pintype "passive"))
    )
    (net (code "43") (name "Net-(R2-Pad2)") (class "Default")
      (node (ref "R2") (pin "2") (pinfunction "2_2") (pintype "passive"))
      (node (ref "R3") (pin "2") (pinfunction "2_2") (pintype "passive"))
      (node (ref "R9") (pin "2") (pinfunction "2_2") (pintype "passive"))
    )
    (net (code "44") (name "PGOOD") (class "Default")
      (node (ref "J2") (pin "5") (pinfunction "5_5") (pintype "passive"))
      (node (ref "J3") (pin "5") (pinfunction "5_5") (pintype "passive"))
    )
    (net (code "47") (name "RELAY_COIL") (class "Default")
      (node (ref "U4") (pin "3") (pinfunction "OUT_3") (pintype "bidirectional"))
      (node (ref "X1") (pin "12") (pinfunction "2_12") (pintype "passive"))
    )
    (net (code "48") (name "RELAY_COM") (class "Default")
      (node (ref "J9") (pin "1") (pinfunction "1_1") (pintype "passive"))
      (node (ref "X1") (pin "9") (pinfunction "P1_9") (pintype "passive"))
    )
    (net (code "49") (name "RELAY_EN") (class "Default")
      (node (ref "JP8") (pin "2") (pinfunction "2_2") (pintype "passive"))
      (node (ref "SJ1") (pin "1") (pinfunction "1_1") (pintype "passive"))
      (node (ref "U4") (pin "1") (pinfunction "IN_1") (pintype "bidirectional"))
    )
    (net (code "50") (name "RELAY_NC") (class "Default")
      (node (ref "X1") (pin "10") (pinfunction "O1_10") (pintype "passive"))
    )
    (net (code "51") (name "RELAY_NO") (class "Default")
      (node (ref "J9") (pin "2") (pinfunction "2_2") (pintype "passive"))
      (node (ref "X1") (pin "8") (pinfunction "S1_8") (pintype "passive"))
    )
    (net (code "52") (name "RS485_A") (class "Default")
      (node (ref "R6") (pin "1") (pinfunction "1_1") (pintype "passive"))
      (node (ref "U3") (pin "6") (pinfunction "A_6") (pintype "bidirectional"))
    )
    (net (code "53") (name "RS485_B") (class "Default")
      (node (ref "R7") (pin "1") (pinfunction "1_1") (pintype "passive"))
      (node (ref "U3") (pin "7") (pinfunction "B_7") (pintype "bidirectional"))
    )
    (net (code "54") (name "RS485_DE{slash}~{RE}") (class "Default")
      (node (ref "JP6") (pin "2") (pinfunction "2_2") (pintype "passive"))
      (node (ref "U3") (pin "2") (pinfunction "/RE_2") (pintype "bidirectional"))
      (node (ref "U3") (pin "3") (pinfunction "DE_3") (pintype "bidirectional"))
    )
    (net (code "57") (name "RTC_BAT") (class "Default")
      (node (ref "J4") (pin "23") (pinfunction "23_23") (pintype "passive"))
      (node (ref "J5") (pin "23") (pinfunction "23_23") (pintype "passive"))
      (node (ref "JP2") (pin "2") (pinfunction "2_2") (pintype "passive"))
    )
    (net (code "58") (name "RTC_EXTI") (class "Default")
      (node (ref "J4") (pin "24") (pinfunction "24_24") (pintype "passive"))
      (node (ref "J5") (pin "24") (pinfunction "24_24") (pintype "passive"))
    )
    (net (code "59") (name "RUN") (class "Default")
      (node (ref "J2") (pin "6") (pinfunction "6_6") (pintype "passive"))
      (node (ref "J3") (pin "6") (pinfunction "6_6") (pintype "passive"))
    )
    (net (code "60") (name "TSOM_A0_SDA") (class "Default")
      (node (ref "J1") (pin "3") (pinfunction "3_3") (pintype "passive"))
      (node (ref "J4") (pin "9") (pinfunction "9_9") (pintype "passive"))
      (node (ref "J5") (pin "9") (pinfunction "9_9") (pintype "passive"))
      (node (ref "U2") (pin "5") (pinfunction "SDA_5") (pintype "bidirectional"))
    )
    (net (code "61") (name "TSOM_A1_SCL") (class "Default")
      (node (ref "J1") (pin "4") (pinfunction "4_4") (pintype "passive"))
      (node (ref "J4") (pin "10") (pinfunction "10_10") (pintype "passive"))
      (node (ref "J5") (pin "10") (pinfunction "10_10") (pintype "passive"))
      (node (ref "U2") (pin "6") (pinfunction "SCL_6") (pintype "input"))
    )
    (net (code "62") (name "TSOM_A2_BUTTON") (class "Default")
      (node (ref "J4") (pin "11") (pinfunction "11_11") (pintype "passive"))
      (node (ref "J5") (pin "11") (pinfunction "11_11") (pintype "passive"))
    )
    (net (code "63") (name "TSOM_A3_BATT_TEMP") (class "Default")
      (node (ref "J4") (pin "12") (pinfunction "12_12") (pintype "passive"))
      (node (ref "J5") (pin "12") (pinfunction "12_12") (pintype "passive"))
    )
    (net (code "64") (name "TSOM_A4") (class "Default")
      (node (ref "J2") (pin "9") (pinfunction "9_9") (pintype "passive"))
      (node (ref "J3") (pin "9") (pinfunction "9_9") (pintype "passive"))
      (node (ref "JP6") (pin "1") (pinfunction "1_1") (pintype "passive"))
    )
    (net (code "65") (name "TSOM_A5") (class "Default")
      (node (ref "J2") (pin "10") (pinfunction "10_10") (pintype "passive"))
      (node (ref "J3") (pin "10") (pinfunction "10_10") (pintype "passive"))
      (node (ref "LED4") (pin "C") (pinfunction "C_C") (pintype "passive"))
      (node (ref "R14") (pin "1") (pinfunction "1_1") (pintype "passive"))
      (node (ref "U5") (pin "6") (pinfunction "6_6") (pintype "bidirectional"))
    )
    (net (code "66") (name "TSOM_A6") (class "Default")
      (node (ref "C4") (pin "1") (pinfunction "1_1") (pintype "bidirectional"))
      (node (ref "D2") (pin "C") (pinfunction "C_C") (pintype "passive"))
      (node (ref "J2") (pin "11") (pinfunction "11_11") (pintype "passive"))
      (node (ref "J3") (pin "11") (pinfunction "11_11") (pintype "passive"))
      (node (ref "R10") (pin "2") (pinfunction "2_2") (pintype "passive"))
      (node (ref "R11") (pin "1") (pinfunction "1_1") (pintype "passive"))
    )
    (net (code "67") (name "TSOM_A7") (class "Default")
      (node (ref "C3") (pin "2") (pinfunction "2_2") (pintype "bidirectional"))
      (node (ref "D1") (pin "C") (pinfunction "C_C") (pintype "passive"))
      (node (ref "J2") (pin "12") (pinfunction "12_12") (pintype "passive"))
      (node (ref "J3") (pin "12") (pinfunction "12_12") (pintype "passive"))
      (node (ref "R9") (pin "1") (pinfunction "1_1") (pintype "passive"))
    )
    (net (code "68") (name "TSOM_NFC2") (class "Default")
      (node (ref "J2") (pin "16") (pinfunction "16_16") (pintype "passive"))
      (node (ref "J3") (pin "16") (pinfunction "16_16") (pintype "passive"))
      (node (ref "SJ1") (pin "2") (pinfunction "2_2") (pintype "passive"))
    )
    (net (code "69") (name "TSOM_RX") (class "Default")
      (node (ref "J4") (pin "21") (pinfunction "21_21") (pintype "passive"))
      (node (ref "J5") (pin "21") (pinfunction "21_21") (pintype "passive"))
      (node (ref "U3") (pin "1") (pinfunction "RO_1") (pintype "bidirectional"))
    )
    (net (code "70") (name "TSOM_TX") (class "Default")
      (node (ref "J4") (pin "22") (pinfunction "22_22") (pintype "passive"))
      (node (ref "J5") (pin "22") (pinfunction "22_22") (pintype "passive"))
      (node (ref "U3") (pin "4") (pinfunction "DI_4") (pintype "bidirectional"))
    )
    (net (code "71") (name "TSOM_USB_N") (class "Default")
      (node (ref "J4") (pin "18") (pinfunction "18_18") (pintype "passive"))
      (node (ref "J5") (pin "18") (pinfunction "18_18") (pintype "passive"))
    )
    (net (code "72") (name "TSOM_USB_P") (class "Default")
      (node (ref "J4") (pin "19") (pinfunction "19_19") (pintype "passive"))
      (node (ref "J5") (pin "19") (pinfunction "19_19") (pintype "passive"))
    )
    (net (code "73") (name "TSOM_USB_VBUS") (class "Default")
      (node (ref "J4") (pin "3") (pinfunction "3_3") (pintype "passive"))
      (node (ref "J5") (pin "3") (pinfunction "3_3") (pintype "passive"))
    )
    (net (code "74") (name "TSOM_VIN") (class "Default")
      (node (ref "J4") (pin "5") (pinfunction "5_5") (pintype "passive"))
      (node (ref "J5") (pin "5") (pinfunction "5_5") (pintype "passive"))
    )
    (net (code "75") (name "VIN") (class "Default")
      (node (ref "CN1") (pin "8") (pinfunction "8_8") (pintype "passive"))
      (node (ref "J2") (pin "1") (pinfunction "1_1") (pintype "passive"))
      (node (ref "J2") (pin "2") (pinfunction "2_2") (pintype "passive"))
      (node (ref "J3") (pin "1") (pinfunction "1_1") (pintype "passive"))
      (node (ref "J3") (pin "2") (pinfunction "2_2") (pintype "passive"))
      (node (ref "PL1") (pin "1") (pinfunction "S_1") (pintype "passive"))
    )
    (net (code "76") (name "unconnected-(D3-C-Pad3)") (class "Default")
      (node (ref "D3") (pin "3") (pinfunction "C_3") (pintype "passive"))
    )
    (net (code "77") (name "unconnected-(D4-C-Pad3)") (class "Default")
      (node (ref "D4") (pin "3") (pinfunction "C_3") (pintype "passive"))
    )
    (net (code "78") (name "unconnected-(D5-C-Pad3)") (class "Default")
      (node (ref "D5") (pin "3") (pinfunction "C_3") (pintype "passive"))
    )
    (net (code "79") (name "unconnected-(D6-C-Pad3)") (class "Default")
      (node (ref "D6") (pin "3") (pinfunction "C_3") (pintype "passive"))
    )
    (net (code "80") (name "unconnected-(X1B-O2-Pad3)") (class "Default")
      (node (ref "X1") (pin "3") (pinfunction "O2_3") (pintype "passive"))
    )
    (net (code "81") (name "unconnected-(X1B-P2-Pad4)") (class "Default")
      (node (ref "X1") (pin "4") (pinfunction "P2_4") (pintype "passive"))
    )
    (net (code "82") (name "unconnected-(X1B-S2-Pad5)") (class "Default")
      (node (ref "X1") (pin "5") (pinfunction "S2_5") (pintype "passive"))
    )
    (net (code "83") (name "~{NFC1_ADP8866_RST}") (class "Default")
      (node (ref "J2") (pin "15") (pinfunction "15_15") (pintype "passive"))
      (node (ref "J3") (pin "15") (pinfunction "15_15") (pintype "passive"))
    )
    (net (code "84") (name "~{TSOM_MODE}") (class "Default")
      (node (ref "J2") (pin "14") (pinfunction "14_14") (pintype "passive"))
      (node (ref "J3") (pin "14") (pinfunction "14_14") (pintype "passive"))
      (node (ref "S2") (pin "1") (pinfunction "1_1") (pintype "passive"))
      (node (ref "S2") (pin "2") (pinfunction "2_2") (pintype "passive"))
    )
    (net (code "85") (name "~{TSOM_RESET}") (class "Default")
      (node (ref "J2") (pin "13") (pinfunction "13_13") (pintype "passive"))
      (node (ref "J3") (pin "13") (pinfunction "13_13") (pintype "passive"))
      (node (ref "S1") (pin "1") (pinfunction "1_1") (pintype "passive"))
      (node (ref "S1") (pin "2") (pinfunction "2_2") (pintype "passive"))
    )
  )
)
